# h-bridge.net
KiCad netlist of a schematic drawn in EAGLE
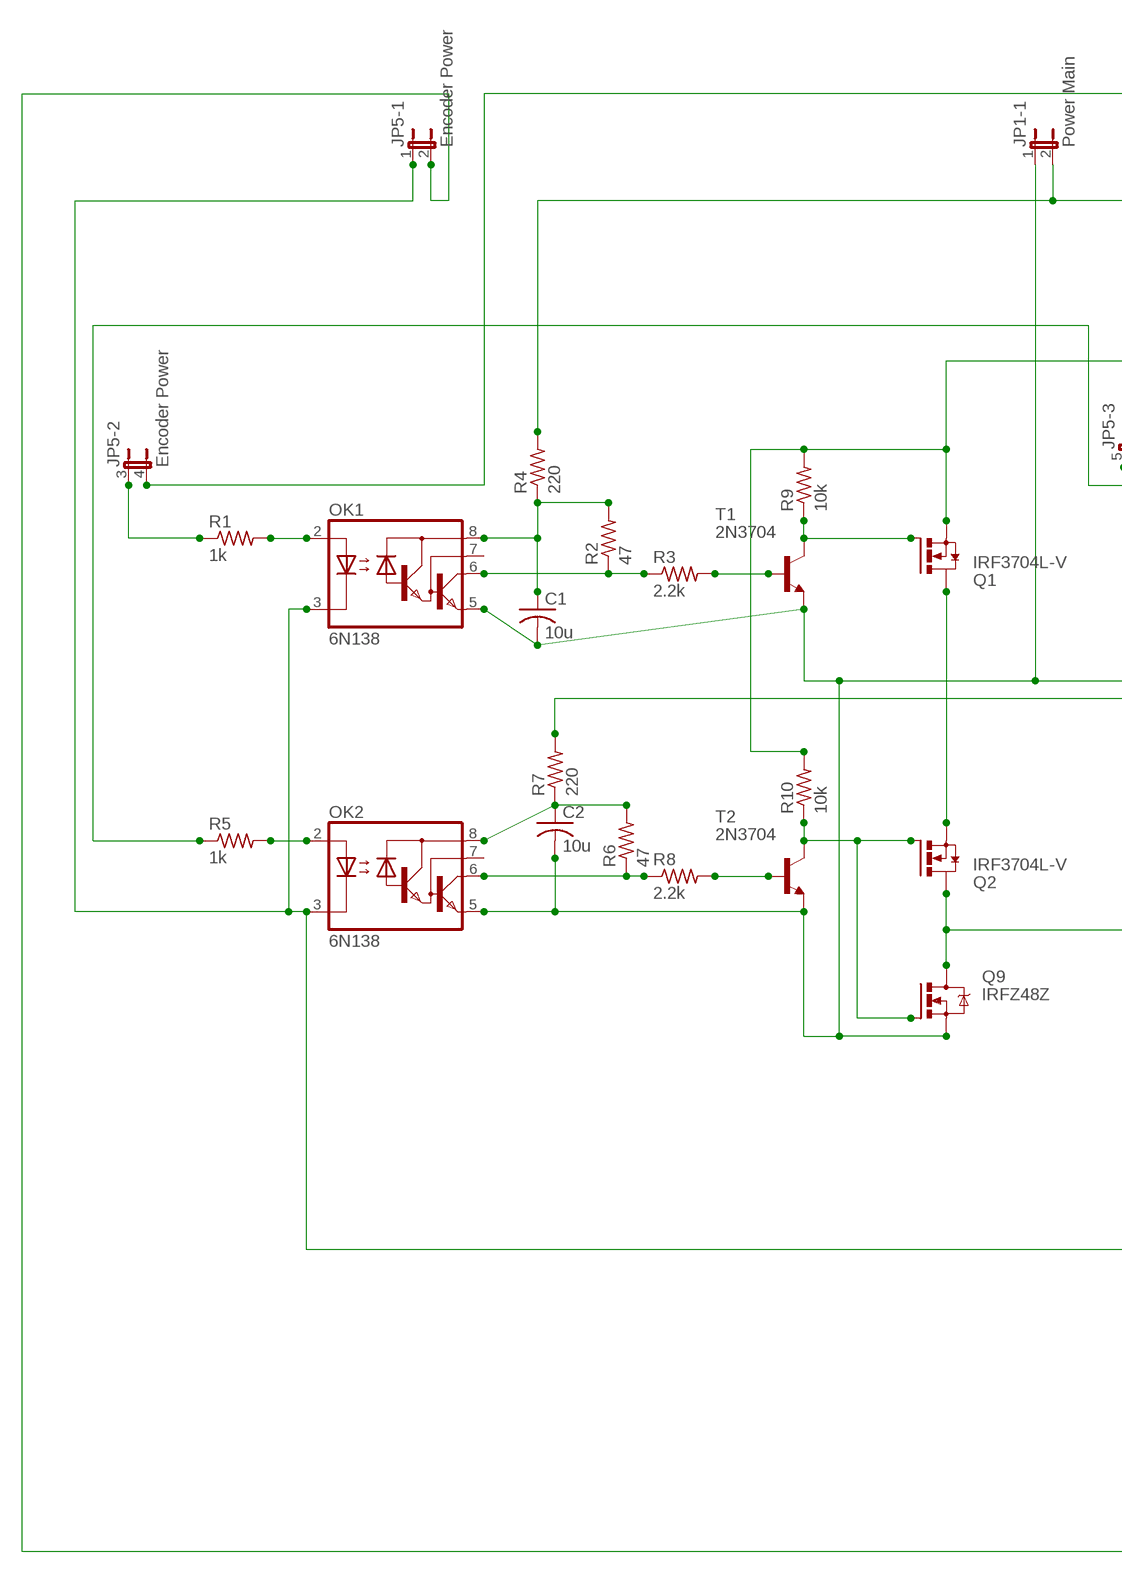
[diagram p0: schematic, sheet 1, part 1 of 2]
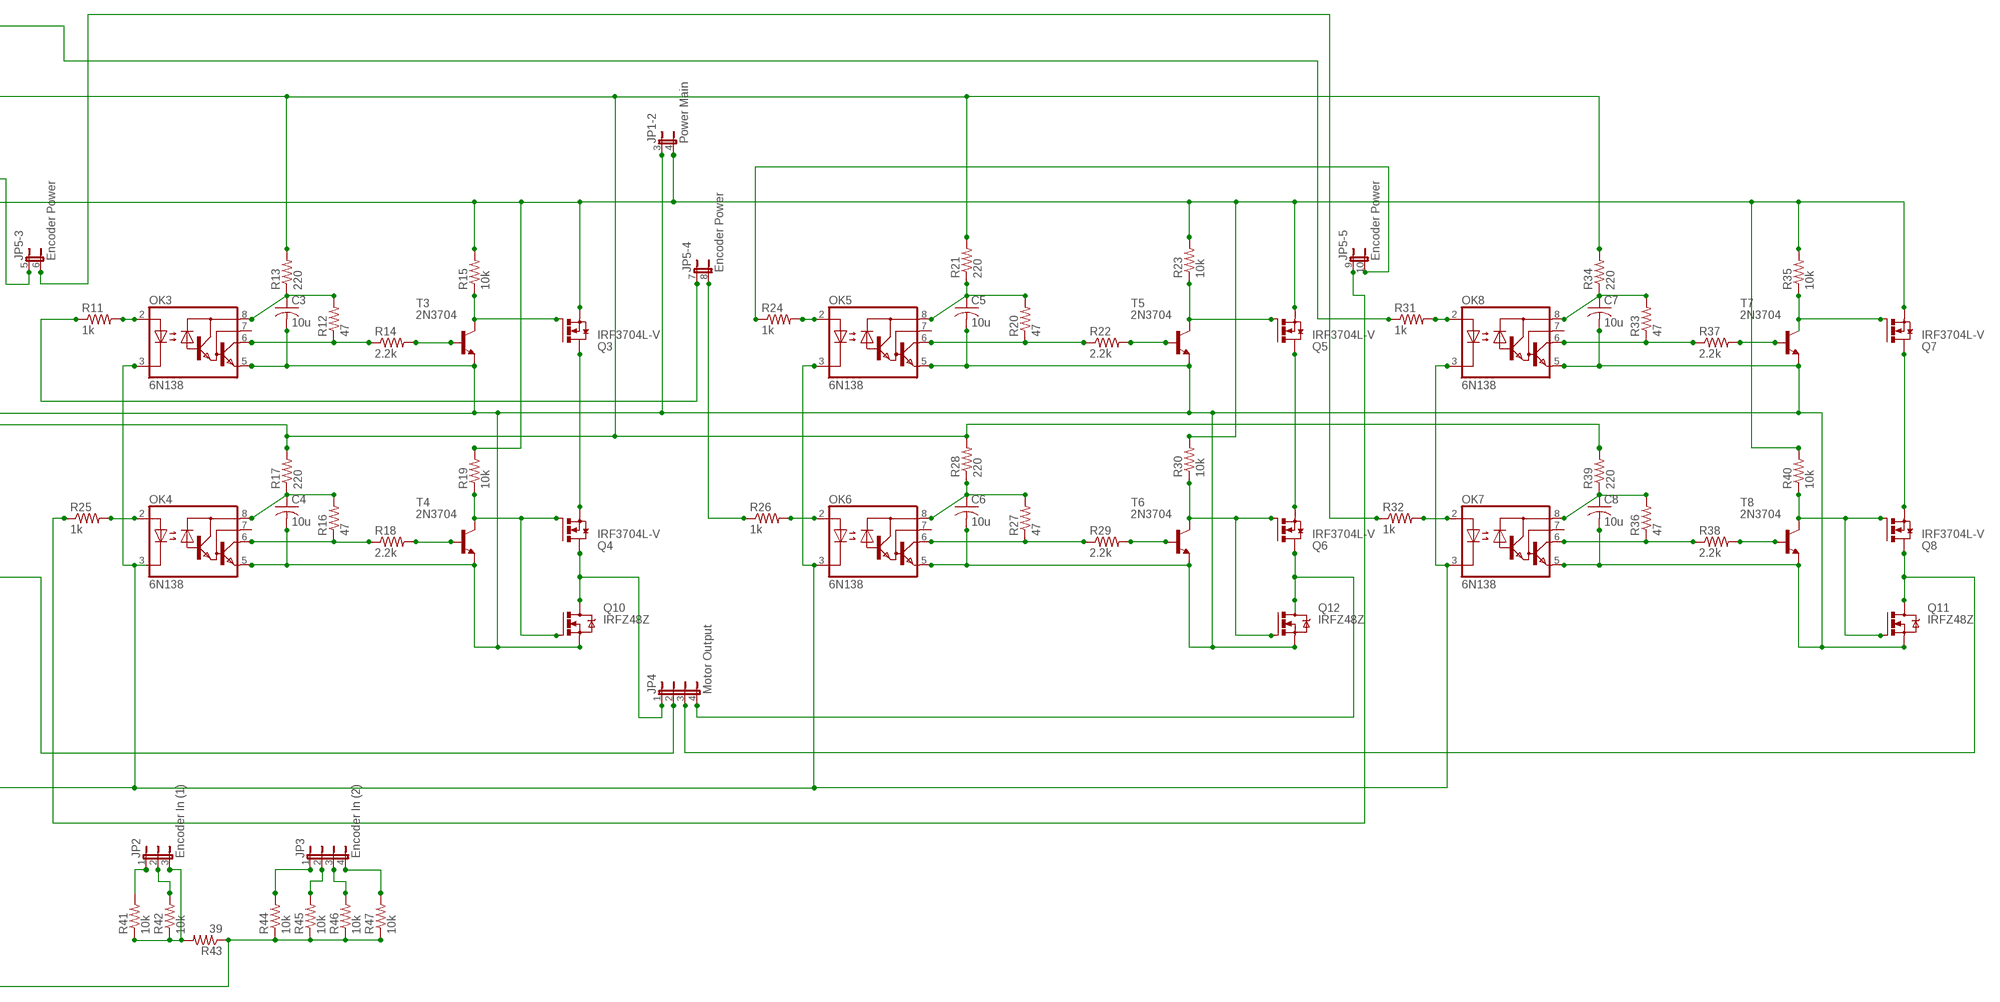
[diagram p1: schematic, sheet 1, part 2 of 2]

(export (version "E")
  (design (tool "Eeschema 10.0.6"))
  (components
    (comp (ref "C1")
      (value "10u")
      (footprint "eagle-import:C025-025X050")
      (libsource (lib "eagle-import") (part "C-US025-025X050"))
    )
    (comp (ref "C2")
      (value "10u")
      (footprint "eagle-import:C025-025X050")
      (libsource (lib "eagle-import") (part "C-US025-025X050"))
    )
    (comp (ref "C3")
      (value "10u")
      (footprint "eagle-import:C025-025X050")
      (libsource (lib "eagle-import") (part "C-US025-025X050"))
    )
    (comp (ref "C4")
      (value "10u")
      (footprint "eagle-import:C025-025X050")
      (libsource (lib "eagle-import") (part "C-US025-025X050"))
    )
    (comp (ref "C5")
      (value "10u")
      (footprint "eagle-import:C025-025X050")
      (libsource (lib "eagle-import") (part "C-US025-025X050"))
    )
    (comp (ref "C6")
      (value "10u")
      (footprint "eagle-import:C025-025X050")
      (libsource (lib "eagle-import") (part "C-US025-025X050"))
    )
    (comp (ref "C7")
      (value "10u")
      (footprint "eagle-import:C025-025X050")
      (libsource (lib "eagle-import") (part "C-US025-025X050"))
    )
    (comp (ref "C8")
      (value "10u")
      (footprint "eagle-import:C025-025X050")
      (libsource (lib "eagle-import") (part "C-US025-025X050"))
    )
    (comp (ref "JP1")
      (value "Power Main")
      (footprint "eagle-import:JP2Q")
      (libsource (lib "eagle-import") (part "JP2QE"))
    )
    (comp (ref "JP2")
      (value "Encoder In (1)")
      (footprint "eagle-import:JP2")
      (libsource (lib "eagle-import") (part "JP2E"))
    )
    (comp (ref "JP3")
      (value "Encoder In (2)")
      (footprint "eagle-import:JP4")
      (libsource (lib "eagle-import") (part "JP4E"))
    )
    (comp (ref "JP4")
      (value "Motor Output")
      (footprint "eagle-import:JP4")
      (libsource (lib "eagle-import") (part "JP4E"))
    )
    (comp (ref "JP5")
      (value "Encoder Power")
      (footprint "eagle-import:JP5Q")
      (libsource (lib "eagle-import") (part "JP5QE"))
    )
    (comp (ref "OK1")
      (value "6N138")
      (footprint "eagle-import:DIL08")
      (fields (field (name "MF") "VISHAY/TELEFUNKEN"))
      (libsource (lib "eagle-import") (part "6N138"))
    )
    (comp (ref "OK2")
      (value "6N138")
      (footprint "eagle-import:DIL08")
      (fields (field (name "MF") "VISHAY/TELEFUNKEN"))
      (libsource (lib "eagle-import") (part "6N138"))
    )
    (comp (ref "OK3")
      (value "6N138")
      (footprint "eagle-import:DIL08")
      (fields (field (name "MF") "VISHAY/TELEFUNKEN"))
      (libsource (lib "eagle-import") (part "6N138"))
    )
    (comp (ref "OK4")
      (value "6N138")
      (footprint "eagle-import:DIL08")
      (fields (field (name "MF") "VISHAY/TELEFUNKEN"))
      (libsource (lib "eagle-import") (part "6N138"))
    )
    (comp (ref "OK5")
      (value "6N138")
      (footprint "eagle-import:DIL08")
      (fields (field (name "MF") "VISHAY/TELEFUNKEN"))
      (libsource (lib "eagle-import") (part "6N138"))
    )
    (comp (ref "OK6")
      (value "6N138")
      (footprint "eagle-import:DIL08")
      (fields (field (name "MF") "VISHAY/TELEFUNKEN"))
      (libsource (lib "eagle-import") (part "6N138"))
    )
    (comp (ref "OK7")
      (value "6N138")
      (footprint "eagle-import:DIL08")
      (fields (field (name "MF") "VISHAY/TELEFUNKEN"))
      (libsource (lib "eagle-import") (part "6N138"))
    )
    (comp (ref "OK8")
      (value "6N138")
      (footprint "eagle-import:DIL08")
      (fields (field (name "MF") "VISHAY/TELEFUNKEN"))
      (libsource (lib "eagle-import") (part "6N138"))
    )
    (comp (ref "Q1")
      (value "IRF3704L-V")
      (footprint "eagle-import:TO262-V")
      (libsource (lib "eagle-import") (part "IRF3704L-V"))
    )
    (comp (ref "Q2")
      (value "IRF3704L-V")
      (footprint "eagle-import:TO262-V")
      (libsource (lib "eagle-import") (part "IRF3704L-V"))
    )
    (comp (ref "Q3")
      (value "IRF3704L-V")
      (footprint "eagle-import:TO262-V")
      (libsource (lib "eagle-import") (part "IRF3704L-V"))
    )
    (comp (ref "Q4")
      (value "IRF3704L-V")
      (footprint "eagle-import:TO262-V")
      (libsource (lib "eagle-import") (part "IRF3704L-V"))
    )
    (comp (ref "Q5")
      (value "IRF3704L-V")
      (footprint "eagle-import:TO262-V")
      (libsource (lib "eagle-import") (part "IRF3704L-V"))
    )
    (comp (ref "Q6")
      (value "IRF3704L-V")
      (footprint "eagle-import:TO262-V")
      (libsource (lib "eagle-import") (part "IRF3704L-V"))
    )
    (comp (ref "Q7")
      (value "IRF3704L-V")
      (footprint "eagle-import:TO262-V")
      (libsource (lib "eagle-import") (part "IRF3704L-V"))
    )
    (comp (ref "Q8")
      (value "IRF3704L-V")
      (footprint "eagle-import:TO262-V")
      (libsource (lib "eagle-import") (part "IRF3704L-V"))
    )
    (comp (ref "Q9")
      (value "IRFZ48Z")
      (footprint "eagle-import:TO220BH")
      (libsource (lib "eagle-import") (part "IRFZ48Z"))
    )
    (comp (ref "Q10")
      (value "IRFZ48Z")
      (footprint "eagle-import:TO220BH")
      (libsource (lib "eagle-import") (part "IRFZ48Z"))
    )
    (comp (ref "Q11")
      (value "IRFZ48Z")
      (footprint "eagle-import:TO220BH")
      (libsource (lib "eagle-import") (part "IRFZ48Z"))
    )
    (comp (ref "Q12")
      (value "IRFZ48Z")
      (footprint "eagle-import:TO220BH")
      (libsource (lib "eagle-import") (part "IRFZ48Z"))
    )
    (comp (ref "R1")
      (value "1k")
      (footprint "eagle-import:0207_10")
      (libsource (lib "eagle-import") (part "R-US_0207/10"))
    )
    (comp (ref "R2")
      (value "47")
      (footprint "eagle-import:0207_10")
      (libsource (lib "eagle-import") (part "R-US_0207/10"))
    )
    (comp (ref "R3")
      (value "2.2k")
      (footprint "eagle-import:0207_10")
      (libsource (lib "eagle-import") (part "R-US_0207/10"))
    )
    (comp (ref "R4")
      (value "220")
      (footprint "eagle-import:0207_10")
      (libsource (lib "eagle-import") (part "R-US_0207/10"))
    )
    (comp (ref "R5")
      (value "1k")
      (footprint "eagle-import:0207_10")
      (libsource (lib "eagle-import") (part "R-US_0207/10"))
    )
    (comp (ref "R6")
      (value "47")
      (footprint "eagle-import:0207_10")
      (libsource (lib "eagle-import") (part "R-US_0207/10"))
    )
    (comp (ref "R7")
      (value "220")
      (footprint "eagle-import:0207_10")
      (libsource (lib "eagle-import") (part "R-US_0207/10"))
    )
    (comp (ref "R8")
      (value "2.2k")
      (footprint "eagle-import:0207_10")
      (libsource (lib "eagle-import") (part "R-US_0207/10"))
    )
    (comp (ref "R9")
      (value "10k")
      (footprint "eagle-import:0207_10")
      (libsource (lib "eagle-import") (part "R-US_0207/10"))
    )
    (comp (ref "R10")
      (value "10k")
      (footprint "eagle-import:0207_10")
      (libsource (lib "eagle-import") (part "R-US_0207/10"))
    )
    (comp (ref "R11")
      (value "1k")
      (footprint "eagle-import:0207_10")
      (libsource (lib "eagle-import") (part "R-US_0207/10"))
    )
    (comp (ref "R12")
      (value "47")
      (footprint "eagle-import:0207_10")
      (libsource (lib "eagle-import") (part "R-US_0207/10"))
    )
    (comp (ref "R13")
      (value "220")
      (footprint "eagle-import:0207_10")
      (libsource (lib "eagle-import") (part "R-US_0207/10"))
    )
    (comp (ref "R14")
      (value "2.2k")
      (footprint "eagle-import:0207_10")
      (libsource (lib "eagle-import") (part "R-US_0207/10"))
    )
    (comp (ref "R15")
      (value "10k")
      (footprint "eagle-import:0207_10")
      (libsource (lib "eagle-import") (part "R-US_0207/10"))
    )
    (comp (ref "R16")
      (value "47")
      (footprint "eagle-import:0207_10")
      (libsource (lib "eagle-import") (part "R-US_0207/10"))
    )
    (comp (ref "R17")
      (value "220")
      (footprint "eagle-import:0207_10")
      (libsource (lib "eagle-import") (part "R-US_0207/10"))
    )
    (comp (ref "R18")
      (value "2.2k")
      (footprint "eagle-import:0207_10")
      (libsource (lib "eagle-import") (part "R-US_0207/10"))
    )
    (comp (ref "R19")
      (value "10k")
      (footprint "eagle-import:0207_10")
      (libsource (lib "eagle-import") (part "R-US_0207/10"))
    )
    (comp (ref "R20")
      (value "47")
      (footprint "eagle-import:0207_10")
      (libsource (lib "eagle-import") (part "R-US_0207/10"))
    )
    (comp (ref "R21")
      (value "220")
      (footprint "eagle-import:0207_10")
      (libsource (lib "eagle-import") (part "R-US_0207/10"))
    )
    (comp (ref "R22")
      (value "2.2k")
      (footprint "eagle-import:0207_10")
      (libsource (lib "eagle-import") (part "R-US_0207/10"))
    )
    (comp (ref "R23")
      (value "10k")
      (footprint "eagle-import:0207_10")
      (libsource (lib "eagle-import") (part "R-US_0207/10"))
    )
    (comp (ref "R24")
      (value "1k")
      (footprint "eagle-import:0207_10")
      (libsource (lib "eagle-import") (part "R-US_0207/10"))
    )
    (comp (ref "R25")
      (value "1k")
      (footprint "eagle-import:0207_10")
      (libsource (lib "eagle-import") (part "R-US_0207/10"))
    )
    (comp (ref "R26")
      (value "1k")
      (footprint "eagle-import:0207_10")
      (libsource (lib "eagle-import") (part "R-US_0207/10"))
    )
    (comp (ref "R27")
      (value "47")
      (footprint "eagle-import:0207_10")
      (libsource (lib "eagle-import") (part "R-US_0207/10"))
    )
    (comp (ref "R28")
      (value "220")
      (footprint "eagle-import:0207_10")
      (libsource (lib "eagle-import") (part "R-US_0207/10"))
    )
    (comp (ref "R29")
      (value "2.2k")
      (footprint "eagle-import:0207_10")
      (libsource (lib "eagle-import") (part "R-US_0207/10"))
    )
    (comp (ref "R30")
      (value "10k")
      (footprint "eagle-import:0207_10")
      (libsource (lib "eagle-import") (part "R-US_0207/10"))
    )
    (comp (ref "R31")
      (value "1k")
      (footprint "eagle-import:0207_10")
      (libsource (lib "eagle-import") (part "R-US_0207/10"))
    )
    (comp (ref "R32")
      (value "1k")
      (footprint "eagle-import:0207_10")
      (libsource (lib "eagle-import") (part "R-US_0207/10"))
    )
    (comp (ref "R33")
      (value "47")
      (footprint "eagle-import:0207_10")
      (libsource (lib "eagle-import") (part "R-US_0207/10"))
    )
    (comp (ref "R34")
      (value "220")
      (footprint "eagle-import:0207_10")
      (libsource (lib "eagle-import") (part "R-US_0207/10"))
    )
    (comp (ref "R35")
      (value "10k")
      (footprint "eagle-import:0207_10")
      (libsource (lib "eagle-import") (part "R-US_0207/10"))
    )
    (comp (ref "R36")
      (value "47")
      (footprint "eagle-import:0207_10")
      (libsource (lib "eagle-import") (part "R-US_0207/10"))
    )
    (comp (ref "R37")
      (value "2.2k")
      (footprint "eagle-import:0207_10")
      (libsource (lib "eagle-import") (part "R-US_0207/10"))
    )
    (comp (ref "R38")
      (value "2.2k")
      (footprint "eagle-import:0207_10")
      (libsource (lib "eagle-import") (part "R-US_0207/10"))
    )
    (comp (ref "R39")
      (value "220")
      (footprint "eagle-import:0207_10")
      (libsource (lib "eagle-import") (part "R-US_0207/10"))
    )
    (comp (ref "R40")
      (value "10k")
      (footprint "eagle-import:0207_10")
      (libsource (lib "eagle-import") (part "R-US_0207/10"))
    )
    (comp (ref "R41")
      (value "10k")
      (footprint "eagle-import:0207_10")
      (libsource (lib "eagle-import") (part "R-US_0207/10"))
    )
    (comp (ref "R42")
      (value "10k")
      (footprint "eagle-import:0207_10")
      (libsource (lib "eagle-import") (part "R-US_0207/10"))
    )
    (comp (ref "R43")
      (value "39")
      (footprint "eagle-import:0207_10")
      (libsource (lib "eagle-import") (part "R-US_0207/10"))
    )
    (comp (ref "R44")
      (value "10k")
      (footprint "eagle-import:0207_10")
      (libsource (lib "eagle-import") (part "R-US_0207/10"))
    )
    (comp (ref "R45")
      (value "10k")
      (footprint "eagle-import:0207_10")
      (libsource (lib "eagle-import") (part "R-US_0207/10"))
    )
    (comp (ref "R46")
      (value "10k")
      (footprint "eagle-import:0207_10")
      (libsource (lib "eagle-import") (part "R-US_0207/10"))
    )
    (comp (ref "R47")
      (value "10k")
      (footprint "eagle-import:0207_10")
      (libsource (lib "eagle-import") (part "R-US_0207/10"))
    )
    (comp (ref "T1")
      (value "2N3704")
      (footprint "eagle-import:TO92")
      (libsource (lib "eagle-import") (part "2N3704"))
    )
    (comp (ref "T2")
      (value "2N3704")
      (footprint "eagle-import:TO92")
      (libsource (lib "eagle-import") (part "2N3704"))
    )
    (comp (ref "T3")
      (value "2N3704")
      (footprint "eagle-import:TO92")
      (libsource (lib "eagle-import") (part "2N3704"))
    )
    (comp (ref "T4")
      (value "2N3704")
      (footprint "eagle-import:TO92")
      (libsource (lib "eagle-import") (part "2N3704"))
    )
    (comp (ref "T5")
      (value "2N3704")
      (footprint "eagle-import:TO92")
      (libsource (lib "eagle-import") (part "2N3704"))
    )
    (comp (ref "T6")
      (value "2N3704")
      (footprint "eagle-import:TO92")
      (libsource (lib "eagle-import") (part "2N3704"))
    )
    (comp (ref "T7")
      (value "2N3704")
      (footprint "eagle-import:TO92")
      (libsource (lib "eagle-import") (part "2N3704"))
    )
    (comp (ref "T8")
      (value "2N3704")
      (footprint "eagle-import:TO92")
      (libsource (lib "eagle-import") (part "2N3704"))
    )
  )
  (nets
    (net (code "1") (name "Net-(JP1-Pad2)") (class "Default")
      (node (ref "JP1") (pin "2") (pinfunction "2_2") (pintype "passive"))
      (node (ref "R13") (pin "2") (pinfunction "2_2") (pintype "passive"))
      (node (ref "R17") (pin "2") (pinfunction "2_2") (pintype "passive"))
      (node (ref "R21") (pin "2") (pinfunction "2_2") (pintype "passive"))
      (node (ref "R28") (pin "2") (pinfunction "2_2") (pintype "passive"))
      (node (ref "R34") (pin "2") (pinfunction "2_2") (pintype "passive"))
      (node (ref "R39") (pin "2") (pinfunction "2_2") (pintype "passive"))
      (node (ref "R4") (pin "2") (pinfunction "2_2") (pintype "passive"))
      (node (ref "R7") (pin "2") (pinfunction "2_2") (pintype "passive"))
    )
    (net (code "2") (name "Net-(JP1B-1)") (class "Default")
      (node (ref "C1") (pin "2") (pinfunction "2_2") (pintype "passive"))
      (node (ref "C2") (pin "2") (pinfunction "2_2") (pintype "passive"))
      (node (ref "C3") (pin "2") (pinfunction "2_2") (pintype "passive"))
      (node (ref "C4") (pin "2") (pinfunction "2_2") (pintype "passive"))
      (node (ref "C5") (pin "2") (pinfunction "2_2") (pintype "passive"))
      (node (ref "C6") (pin "2") (pinfunction "2_2") (pintype "passive"))
      (node (ref "C7") (pin "2") (pinfunction "2_2") (pintype "passive"))
      (node (ref "C8") (pin "2") (pinfunction "2_2") (pintype "passive"))
      (node (ref "JP1") (pin "1") (pinfunction "1_1") (pintype "passive"))
      (node (ref "JP1") (pin "3") (pinfunction "1_3") (pintype "passive"))
      (node (ref "OK1") (pin "5") (pinfunction "GND_5") (pintype "passive"))
      (node (ref "OK2") (pin "5") (pinfunction "GND_5") (pintype "passive"))
      (node (ref "OK3") (pin "5") (pinfunction "GND_5") (pintype "passive"))
      (node (ref "OK4") (pin "5") (pinfunction "GND_5") (pintype "passive"))
      (node (ref "OK5") (pin "5") (pinfunction "GND_5") (pintype "passive"))
      (node (ref "OK6") (pin "5") (pinfunction "GND_5") (pintype "passive"))
      (node (ref "OK7") (pin "5") (pinfunction "GND_5") (pintype "passive"))
      (node (ref "OK8") (pin "5") (pinfunction "GND_5") (pintype "passive"))
      (node (ref "Q10") (pin "S") (pinfunction "S_S") (pintype "passive"))
      (node (ref "Q11") (pin "S") (pinfunction "S_S") (pintype "passive"))
      (node (ref "Q12") (pin "S") (pinfunction "S_S") (pintype "passive"))
      (node (ref "Q9") (pin "S") (pinfunction "S_S") (pintype "passive"))
      (node (ref "T1") (pin "3") (pinfunction "E_3") (pintype "passive"))
      (node (ref "T2") (pin "3") (pinfunction "E_3") (pintype "passive"))
      (node (ref "T3") (pin "3") (pinfunction "E_3") (pintype "passive"))
      (node (ref "T4") (pin "3") (pinfunction "E_3") (pintype "passive"))
      (node (ref "T5") (pin "3") (pinfunction "E_3") (pintype "passive"))
      (node (ref "T6") (pin "3") (pinfunction "E_3") (pintype "passive"))
      (node (ref "T7") (pin "3") (pinfunction "E_3") (pintype "passive"))
      (node (ref "T8") (pin "3") (pinfunction "E_3") (pintype "passive"))
    )
    (net (code "3") (name "Net-(JP1B-2)") (class "Default")
      (node (ref "JP1") (pin "4") (pinfunction "2_4") (pintype "passive"))
      (node (ref "Q1") (pin "3") (pinfunction "S_3") (pintype "passive"))
      (node (ref "Q3") (pin "3") (pinfunction "S_3") (pintype "passive"))
      (node (ref "Q5") (pin "3") (pinfunction "S_3") (pintype "passive"))
      (node (ref "Q7") (pin "3") (pinfunction "S_3") (pintype "passive"))
      (node (ref "R10") (pin "2") (pinfunction "2_2") (pintype "passive"))
      (node (ref "R15") (pin "2") (pinfunction "2_2") (pintype "passive"))
      (node (ref "R19") (pin "2") (pinfunction "2_2") (pintype "passive"))
      (node (ref "R23") (pin "2") (pinfunction "2_2") (pintype "passive"))
      (node (ref "R30") (pin "2") (pinfunction "2_2") (pintype "passive"))
      (node (ref "R35") (pin "2") (pinfunction "2_2") (pintype "passive"))
      (node (ref "R40") (pin "2") (pinfunction "2_2") (pintype "passive"))
      (node (ref "R9") (pin "2") (pinfunction "2_2") (pintype "passive"))
    )
    (net (code "4") (name "Net-(JP2-Pad1)") (class "Default")
      (node (ref "JP2") (pin "1") (pinfunction "1_1") (pintype "passive"))
      (node (ref "R41") (pin "2") (pinfunction "2_2") (pintype "passive"))
    )
    (net (code "5") (name "Net-(JP2-Pad2)") (class "Default")
      (node (ref "JP2") (pin "2") (pinfunction "2_2") (pintype "passive"))
      (node (ref "R42") (pin "2") (pinfunction "2_2") (pintype "passive"))
    )
    (net (code "6") (name "Net-(JP2-Pad3)") (class "Default")
      (node (ref "JP2") (pin "3") (pinfunction "3_3") (pintype "passive"))
      (node (ref "R41") (pin "1") (pinfunction "1_1") (pintype "passive"))
      (node (ref "R42") (pin "1") (pinfunction "1_1") (pintype "passive"))
      (node (ref "R43") (pin "2") (pinfunction "2_2") (pintype "passive"))
    )
    (net (code "7") (name "Net-(JP3-Pad1)") (class "Default")
      (node (ref "JP3") (pin "1") (pinfunction "1_1") (pintype "passive"))
      (node (ref "R44") (pin "2") (pinfunction "2_2") (pintype "passive"))
    )
    (net (code "8") (name "Net-(JP3-Pad2)") (class "Default")
      (node (ref "JP3") (pin "2") (pinfunction "2_2") (pintype "passive"))
      (node (ref "R45") (pin "2") (pinfunction "2_2") (pintype "passive"))
    )
    (net (code "9") (name "Net-(JP3-Pad3)") (class "Default")
      (node (ref "JP3") (pin "3") (pinfunction "3_3") (pintype "passive"))
      (node (ref "R46") (pin "2") (pinfunction "2_2") (pintype "passive"))
    )
    (net (code "10") (name "Net-(JP3-Pad4)") (class "Default")
      (node (ref "JP3") (pin "4") (pinfunction "4_4") (pintype "passive"))
      (node (ref "R47") (pin "2") (pinfunction "2_2") (pintype "passive"))
    )
    (net (code "11") (name "Net-(JP5-Pad2)") (class "Default")
      (node (ref "JP5") (pin "2") (pinfunction "2_2") (pintype "passive"))
      (node (ref "R43") (pin "1") (pinfunction "1_1") (pintype "passive"))
      (node (ref "R44") (pin "1") (pinfunction "1_1") (pintype "passive"))
      (node (ref "R45") (pin "1") (pinfunction "1_1") (pintype "passive"))
      (node (ref "R46") (pin "1") (pinfunction "1_1") (pintype "passive"))
      (node (ref "R47") (pin "1") (pinfunction "1_1") (pintype "passive"))
    )
    (net (code "12") (name "Net-(JP5B-1)") (class "Default")
      (node (ref "JP5") (pin "3") (pinfunction "1_3") (pintype "passive"))
      (node (ref "R1") (pin "1") (pinfunction "1_1") (pintype "passive"))
    )
    (net (code "13") (name "Net-(JP5B-2)") (class "Default")
      (node (ref "JP5") (pin "4") (pinfunction "2_4") (pintype "passive"))
      (node (ref "R31") (pin "1") (pinfunction "1_1") (pintype "passive"))
    )
    (net (code "14") (name "Net-(JP5C-1)") (class "Default")
      (node (ref "JP5") (pin "5") (pinfunction "1_5") (pintype "passive"))
      (node (ref "R5") (pin "1") (pinfunction "1_1") (pintype "passive"))
    )
    (net (code "15") (name "Net-(JP5C-2)") (class "Default")
      (node (ref "JP5") (pin "6") (pinfunction "2_6") (pintype "passive"))
      (node (ref "R32") (pin "1") (pinfunction "1_1") (pintype "passive"))
    )
    (net (code "16") (name "Net-(JP5D-1)") (class "Default")
      (node (ref "JP5") (pin "7") (pinfunction "1_7") (pintype "passive"))
      (node (ref "R11") (pin "1") (pinfunction "1_1") (pintype "passive"))
    )
    (net (code "17") (name "Net-(JP5D-2)") (class "Default")
      (node (ref "JP5") (pin "8") (pinfunction "2_8") (pintype "passive"))
      (node (ref "R26") (pin "1") (pinfunction "1_1") (pintype "passive"))
    )
    (net (code "18") (name "Net-(JP5E-1)") (class "Default")
      (node (ref "JP5") (pin "9") (pinfunction "1_9") (pintype "passive"))
      (node (ref "R25") (pin "1") (pinfunction "1_1") (pintype "passive"))
    )
    (net (code "19") (name "Net-(JP5E-2)") (class "Default")
      (node (ref "JP5") (pin "10") (pinfunction "2_10") (pintype "passive"))
      (node (ref "R24") (pin "1") (pinfunction "1_1") (pintype "passive"))
    )
    (net (code "20") (name "Net-(OK1-A)") (class "Default")
      (node (ref "OK1") (pin "2") (pinfunction "A_2") (pintype "passive"))
      (node (ref "R1") (pin "2") (pinfunction "2_2") (pintype "passive"))
    )
    (net (code "21") (name "Net-(OK1-C)") (class "Default")
      (node (ref "JP5") (pin "1") (pinfunction "1_1") (pintype "passive"))
      (node (ref "OK1") (pin "3") (pinfunction "C_3") (pintype "passive"))
      (node (ref "OK2") (pin "3") (pinfunction "C_3") (pintype "passive"))
      (node (ref "OK3") (pin "3") (pinfunction "C_3") (pintype "passive"))
      (node (ref "OK4") (pin "3") (pinfunction "C_3") (pintype "passive"))
      (node (ref "OK5") (pin "3") (pinfunction "C_3") (pintype "passive"))
      (node (ref "OK6") (pin "3") (pinfunction "C_3") (pintype "passive"))
      (node (ref "OK7") (pin "3") (pinfunction "C_3") (pintype "passive"))
      (node (ref "OK8") (pin "3") (pinfunction "C_3") (pintype "passive"))
    )
    (net (code "22") (name "Net-(OK1-VCC)") (class "Default")
      (node (ref "C1") (pin "1") (pinfunction "1_1") (pintype "passive"))
      (node (ref "OK1") (pin "8") (pinfunction "VCC_8") (pintype "passive"))
      (node (ref "R2") (pin "2") (pinfunction "2_2") (pintype "passive"))
      (node (ref "R4") (pin "1") (pinfunction "1_1") (pintype "passive"))
    )
    (net (code "23") (name "Net-(OK1-VO)") (class "Default")
      (node (ref "OK1") (pin "6") (pinfunction "VO_6") (pintype "passive"))
      (node (ref "R2") (pin "1") (pinfunction "1_1") (pintype "passive"))
      (node (ref "R3") (pin "1") (pinfunction "1_1") (pintype "passive"))
    )
    (net (code "24") (name "Net-(OK2-A)") (class "Default")
      (node (ref "OK2") (pin "2") (pinfunction "A_2") (pintype "passive"))
      (node (ref "R5") (pin "2") (pinfunction "2_2") (pintype "passive"))
    )
    (net (code "25") (name "Net-(OK2-VCC)") (class "Default")
      (node (ref "C2") (pin "1") (pinfunction "1_1") (pintype "passive"))
      (node (ref "OK2") (pin "8") (pinfunction "VCC_8") (pintype "passive"))
      (node (ref "R6") (pin "2") (pinfunction "2_2") (pintype "passive"))
      (node (ref "R7") (pin "1") (pinfunction "1_1") (pintype "passive"))
    )
    (net (code "26") (name "Net-(OK2-VO)") (class "Default")
      (node (ref "OK2") (pin "6") (pinfunction "VO_6") (pintype "passive"))
      (node (ref "R6") (pin "1") (pinfunction "1_1") (pintype "passive"))
      (node (ref "R8") (pin "1") (pinfunction "1_1") (pintype "passive"))
    )
    (net (code "27") (name "Net-(OK3-A)") (class "Default")
      (node (ref "OK3") (pin "2") (pinfunction "A_2") (pintype "passive"))
      (node (ref "R11") (pin "2") (pinfunction "2_2") (pintype "passive"))
    )
    (net (code "28") (name "Net-(OK3-VCC)") (class "Default")
      (node (ref "C3") (pin "1") (pinfunction "1_1") (pintype "passive"))
      (node (ref "OK3") (pin "8") (pinfunction "VCC_8") (pintype "passive"))
      (node (ref "R12") (pin "2") (pinfunction "2_2") (pintype "passive"))
      (node (ref "R13") (pin "1") (pinfunction "1_1") (pintype "passive"))
    )
    (net (code "29") (name "Net-(OK3-VO)") (class "Default")
      (node (ref "OK3") (pin "6") (pinfunction "VO_6") (pintype "passive"))
      (node (ref "R12") (pin "1") (pinfunction "1_1") (pintype "passive"))
      (node (ref "R14") (pin "1") (pinfunction "1_1") (pintype "passive"))
    )
    (net (code "30") (name "Net-(OK4-A)") (class "Default")
      (node (ref "OK4") (pin "2") (pinfunction "A_2") (pintype "passive"))
      (node (ref "R25") (pin "2") (pinfunction "2_2") (pintype "passive"))
    )
    (net (code "31") (name "Net-(OK4-VCC)") (class "Default")
      (node (ref "C4") (pin "1") (pinfunction "1_1") (pintype "passive"))
      (node (ref "OK4") (pin "8") (pinfunction "VCC_8") (pintype "passive"))
      (node (ref "R16") (pin "2") (pinfunction "2_2") (pintype "passive"))
      (node (ref "R17") (pin "1") (pinfunction "1_1") (pintype "passive"))
    )
    (net (code "32") (name "Net-(OK4-VO)") (class "Default")
      (node (ref "OK4") (pin "6") (pinfunction "VO_6") (pintype "passive"))
      (node (ref "R16") (pin "1") (pinfunction "1_1") (pintype "passive"))
      (node (ref "R18") (pin "1") (pinfunction "1_1") (pintype "passive"))
    )
    (net (code "33") (name "Net-(OK5-A)") (class "Default")
      (node (ref "OK5") (pin "2") (pinfunction "A_2") (pintype "passive"))
      (node (ref "R24") (pin "2") (pinfunction "2_2") (pintype "passive"))
    )
    (net (code "34") (name "Net-(OK5-VCC)") (class "Default")
      (node (ref "C5") (pin "1") (pinfunction "1_1") (pintype "passive"))
      (node (ref "OK5") (pin "8") (pinfunction "VCC_8") (pintype "passive"))
      (node (ref "R20") (pin "2") (pinfunction "2_2") (pintype "passive"))
      (node (ref "R21") (pin "1") (pinfunction "1_1") (pintype "passive"))
    )
    (net (code "35") (name "Net-(OK5-VO)") (class "Default")
      (node (ref "OK5") (pin "6") (pinfunction "VO_6") (pintype "passive"))
      (node (ref "R20") (pin "1") (pinfunction "1_1") (pintype "passive"))
      (node (ref "R22") (pin "1") (pinfunction "1_1") (pintype "passive"))
    )
    (net (code "36") (name "Net-(OK6-A)") (class "Default")
      (node (ref "OK6") (pin "2") (pinfunction "A_2") (pintype "passive"))
      (node (ref "R26") (pin "2") (pinfunction "2_2") (pintype "passive"))
    )
    (net (code "37") (name "Net-(OK6-VCC)") (class "Default")
      (node (ref "C6") (pin "1") (pinfunction "1_1") (pintype "passive"))
      (node (ref "OK6") (pin "8") (pinfunction "VCC_8") (pintype "passive"))
      (node (ref "R27") (pin "2") (pinfunction "2_2") (pintype "passive"))
      (node (ref "R28") (pin "1") (pinfunction "1_1") (pintype "passive"))
    )
    (net (code "38") (name "Net-(OK6-VO)") (class "Default")
      (node (ref "OK6") (pin "6") (pinfunction "VO_6") (pintype "passive"))
      (node (ref "R27") (pin "1") (pinfunction "1_1") (pintype "passive"))
      (node (ref "R29") (pin "1") (pinfunction "1_1") (pintype "passive"))
    )
    (net (code "39") (name "Net-(OK7-A)") (class "Default")
      (node (ref "OK7") (pin "2") (pinfunction "A_2") (pintype "passive"))
      (node (ref "R32") (pin "2") (pinfunction "2_2") (pintype "passive"))
    )
    (net (code "40") (name "Net-(OK7-VCC)") (class "Default")
      (node (ref "C8") (pin "1") (pinfunction "1_1") (pintype "passive"))
      (node (ref "OK7") (pin "8") (pinfunction "VCC_8") (pintype "passive"))
      (node (ref "R36") (pin "2") (pinfunction "2_2") (pintype "passive"))
      (node (ref "R39") (pin "1") (pinfunction "1_1") (pintype "passive"))
    )
    (net (code "41") (name "Net-(OK7-VO)") (class "Default")
      (node (ref "OK7") (pin "6") (pinfunction "VO_6") (pintype "passive"))
      (node (ref "R36") (pin "1") (pinfunction "1_1") (pintype "passive"))
      (node (ref "R38") (pin "1") (pinfunction "1_1") (pintype "passive"))
    )
    (net (code "42") (name "Net-(OK8-A)") (class "Default")
      (node (ref "OK8") (pin "2") (pinfunction "A_2") (pintype "passive"))
      (node (ref "R31") (pin "2") (pinfunction "2_2") (pintype "passive"))
    )
    (net (code "43") (name "Net-(OK8-VCC)") (class "Default")
      (node (ref "C7") (pin "1") (pinfunction "1_1") (pintype "passive"))
      (node (ref "OK8") (pin "8") (pinfunction "VCC_8") (pintype "passive"))
      (node (ref "R33") (pin "2") (pinfunction "2_2") (pintype "passive"))
      (node (ref "R34") (pin "1") (pinfunction "1_1") (pintype "passive"))
    )
    (net (code "44") (name "Net-(OK8-VO)") (class "Default")
      (node (ref "OK8") (pin "6") (pinfunction "VO_6") (pintype "passive"))
      (node (ref "R33") (pin "1") (pinfunction "1_1") (pintype "passive"))
      (node (ref "R37") (pin "1") (pinfunction "1_1") (pintype "passive"))
    )
    (net (code "45") (name "Net-(Q1-D)") (class "Default")
      (node (ref "Q1") (pin "2") (pinfunction "D_2") (pintype "passive"))
      (node (ref "Q2") (pin "3") (pinfunction "S_3") (pintype "passive"))
    )
    (net (code "46") (name "Net-(Q1-G)") (class "Default")
      (node (ref "Q1") (pin "1") (pinfunction "G_1") (pintype "passive"))
      (node (ref "R9") (pin "1") (pinfunction "1_1") (pintype "passive"))
      (node (ref "T1") (pin "2") (pinfunction "C_2") (pintype "passive"))
    )
    (net (code "47") (name "Net-(Q2-D)") (class "Default")
      (node (ref "JP4") (pin "2") (pinfunction "2_2") (pintype "passive"))
      (node (ref "Q2") (pin "2") (pinfunction "D_2") (pintype "passive"))
      (node (ref "Q9") (pin "D") (pinfunction "D_D") (pintype "passive"))
    )
    (net (code "48") (name "Net-(Q2-G)") (class "Default")
      (node (ref "Q2") (pin "1") (pinfunction "G_1") (pintype "passive"))
      (node (ref "Q9") (pin "G") (pinfunction "G_G") (pintype "passive"))
      (node (ref "R10") (pin "1") (pinfunction "1_1") (pintype "passive"))
      (node (ref "T2") (pin "2") (pinfunction "C_2") (pintype "passive"))
    )
    (net (code "49") (name "Net-(Q3-D)") (class "Default")
      (node (ref "Q3") (pin "2") (pinfunction "D_2") (pintype "passive"))
      (node (ref "Q4") (pin "3") (pinfunction "S_3") (pintype "passive"))
    )
    (net (code "50") (name "Net-(Q3-G)") (class "Default")
      (node (ref "Q3") (pin "1") (pinfunction "G_1") (pintype "passive"))
      (node (ref "R15") (pin "1") (pinfunction "1_1") (pintype "passive"))
      (node (ref "T3") (pin "2") (pinfunction "C_2") (pintype "passive"))
    )
    (net (code "51") (name "Net-(Q4-D)") (class "Default")
      (node (ref "JP4") (pin "1") (pinfunction "1_1") (pintype "passive"))
      (node (ref "Q10") (pin "D") (pinfunction "D_D") (pintype "passive"))
      (node (ref "Q4") (pin "2") (pinfunction "D_2") (pintype "passive"))
    )
    (net (code "52") (name "Net-(Q4-G)") (class "Default")
      (node (ref "Q10") (pin "G") (pinfunction "G_G") (pintype "passive"))
      (node (ref "Q4") (pin "1") (pinfunction "G_1") (pintype "passive"))
      (node (ref "R19") (pin "1") (pinfunction "1_1") (pintype "passive"))
      (node (ref "T4") (pin "2") (pinfunction "C_2") (pintype "passive"))
    )
    (net (code "53") (name "Net-(Q5-D)") (class "Default")
      (node (ref "Q5") (pin "2") (pinfunction "D_2") (pintype "passive"))
      (node (ref "Q6") (pin "3") (pinfunction "S_3") (pintype "passive"))
    )
    (net (code "54") (name "Net-(Q5-G)") (class "Default")
      (node (ref "Q5") (pin "1") (pinfunction "G_1") (pintype "passive"))
      (node (ref "R23") (pin "1") (pinfunction "1_1") (pintype "passive"))
      (node (ref "T5") (pin "2") (pinfunction "C_2") (pintype "passive"))
    )
    (net (code "55") (name "Net-(Q6-D)") (class "Default")
      (node (ref "JP4") (pin "4") (pinfunction "4_4") (pintype "passive"))
      (node (ref "Q12") (pin "D") (pinfunction "D_D") (pintype "passive"))
      (node (ref "Q6") (pin "2") (pinfunction "D_2") (pintype "passive"))
    )
    (net (code "56") (name "Net-(Q6-G)") (class "Default")
      (node (ref "Q12") (pin "G") (pinfunction "G_G") (pintype "passive"))
      (node (ref "Q6") (pin "1") (pinfunction "G_1") (pintype "passive"))
      (node (ref "R30") (pin "1") (pinfunction "1_1") (pintype "passive"))
      (node (ref "T6") (pin "2") (pinfunction "C_2") (pintype "passive"))
    )
    (net (code "57") (name "Net-(Q7-D)") (class "Default")
      (node (ref "Q7") (pin "2") (pinfunction "D_2") (pintype "passive"))
      (node (ref "Q8") (pin "3") (pinfunction "S_3") (pintype "passive"))
    )
    (net (code "58") (name "Net-(Q7-G)") (class "Default")
      (node (ref "Q7") (pin "1") (pinfunction "G_1") (pintype "passive"))
      (node (ref "R35") (pin "1") (pinfunction "1_1") (pintype "passive"))
      (node (ref "T7") (pin "2") (pinfunction "C_2") (pintype "passive"))
    )
    (net (code "59") (name "Net-(Q8-D)") (class "Default")
      (node (ref "JP4") (pin "3") (pinfunction "3_3") (pintype "passive"))
      (node (ref "Q11") (pin "D") (pinfunction "D_D") (pintype "passive"))
      (node (ref "Q8") (pin "2") (pinfunction "D_2") (pintype "passive"))
    )
    (net (code "60") (name "Net-(Q8-G)") (class "Default")
      (node (ref "Q11") (pin "G") (pinfunction "G_G") (pintype "passive"))
      (node (ref "Q8") (pin "1") (pinfunction "G_1") (pintype "passive"))
      (node (ref "R40") (pin "1") (pinfunction "1_1") (pintype "passive"))
      (node (ref "T8") (pin "2") (pinfunction "C_2") (pintype "passive"))
    )
    (net (code "61") (name "Net-(T1-B)") (class "Default")
      (node (ref "R3") (pin "2") (pinfunction "2_2") (pintype "passive"))
      (node (ref "T1") (pin "1") (pinfunction "B_1") (pintype "passive"))
    )
    (net (code "62") (name "Net-(T2-B)") (class "Default")
      (node (ref "R8") (pin "2") (pinfunction "2_2") (pintype "passive"))
      (node (ref "T2") (pin "1") (pinfunction "B_1") (pintype "passive"))
    )
    (net (code "63") (name "Net-(T3-B)") (class "Default")
      (node (ref "R14") (pin "2") (pinfunction "2_2") (pintype "passive"))
      (node (ref "T3") (pin "1") (pinfunction "B_1") (pintype "passive"))
    )
    (net (code "64") (name "Net-(T4-B)") (class "Default")
      (node (ref "R18") (pin "2") (pinfunction "2_2") (pintype "passive"))
      (node (ref "T4") (pin "1") (pinfunction "B_1") (pintype "passive"))
    )
    (net (code "65") (name "Net-(T5-B)") (class "Default")
      (node (ref "R22") (pin "2") (pinfunction "2_2") (pintype "passive"))
      (node (ref "T5") (pin "1") (pinfunction "B_1") (pintype "passive"))
    )
    (net (code "66") (name "Net-(T6-B)") (class "Default")
      (node (ref "R29") (pin "2") (pinfunction "2_2") (pintype "passive"))
      (node (ref "T6") (pin "1") (pinfunction "B_1") (pintype "passive"))
    )
    (net (code "67") (name "Net-(T7-B)") (class "Default")
      (node (ref "R37") (pin "2") (pinfunction "2_2") (pintype "passive"))
      (node (ref "T7") (pin "1") (pinfunction "B_1") (pintype "passive"))
    )
    (net (code "68") (name "Net-(T8-B)") (class "Default")
      (node (ref "R38") (pin "2") (pinfunction "2_2") (pintype "passive"))
      (node (ref "T8") (pin "1") (pinfunction "B_1") (pintype "passive"))
    )
    (net (code "69") (name "unconnected-(OK1-VB-Pad7)") (class "Default")
      (node (ref "OK1") (pin "7") (pinfunction "VB_7") (pintype "passive"))
    )
    (net (code "70") (name "unconnected-(OK2-VB-Pad7)") (class "Default")
      (node (ref "OK2") (pin "7") (pinfunction "VB_7") (pintype "passive"))
    )
    (net (code "71") (name "unconnected-(OK3-VB-Pad7)") (class "Default")
      (node (ref "OK3") (pin "7") (pinfunction "VB_7") (pintype "passive"))
    )
    (net (code "72") (name "unconnected-(OK4-VB-Pad7)") (class "Default")
      (node (ref "OK4") (pin "7") (pinfunction "VB_7") (pintype "passive"))
    )
    (net (code "73") (name "unconnected-(OK5-VB-Pad7)") (class "Default")
      (node (ref "OK5") (pin "7") (pinfunction "VB_7") (pintype "passive"))
    )
    (net (code "74") (name "unconnected-(OK6-VB-Pad7)") (class "Default")
      (node (ref "OK6") (pin "7") (pinfunction "VB_7") (pintype "passive"))
    )
    (net (code "75") (name "unconnected-(OK7-VB-Pad7)") (class "Default")
      (node (ref "OK7") (pin "7") (pinfunction "VB_7") (pintype "passive"))
    )
    (net (code "76") (name "unconnected-(OK8-VB-Pad7)") (class "Default")
      (node (ref "OK8") (pin "7") (pinfunction "VB_7") (pintype "passive"))
    )
  )
)
